# 04_Motor_Driver.net
KiCad netlist of a schematic drawn in Altium Designer
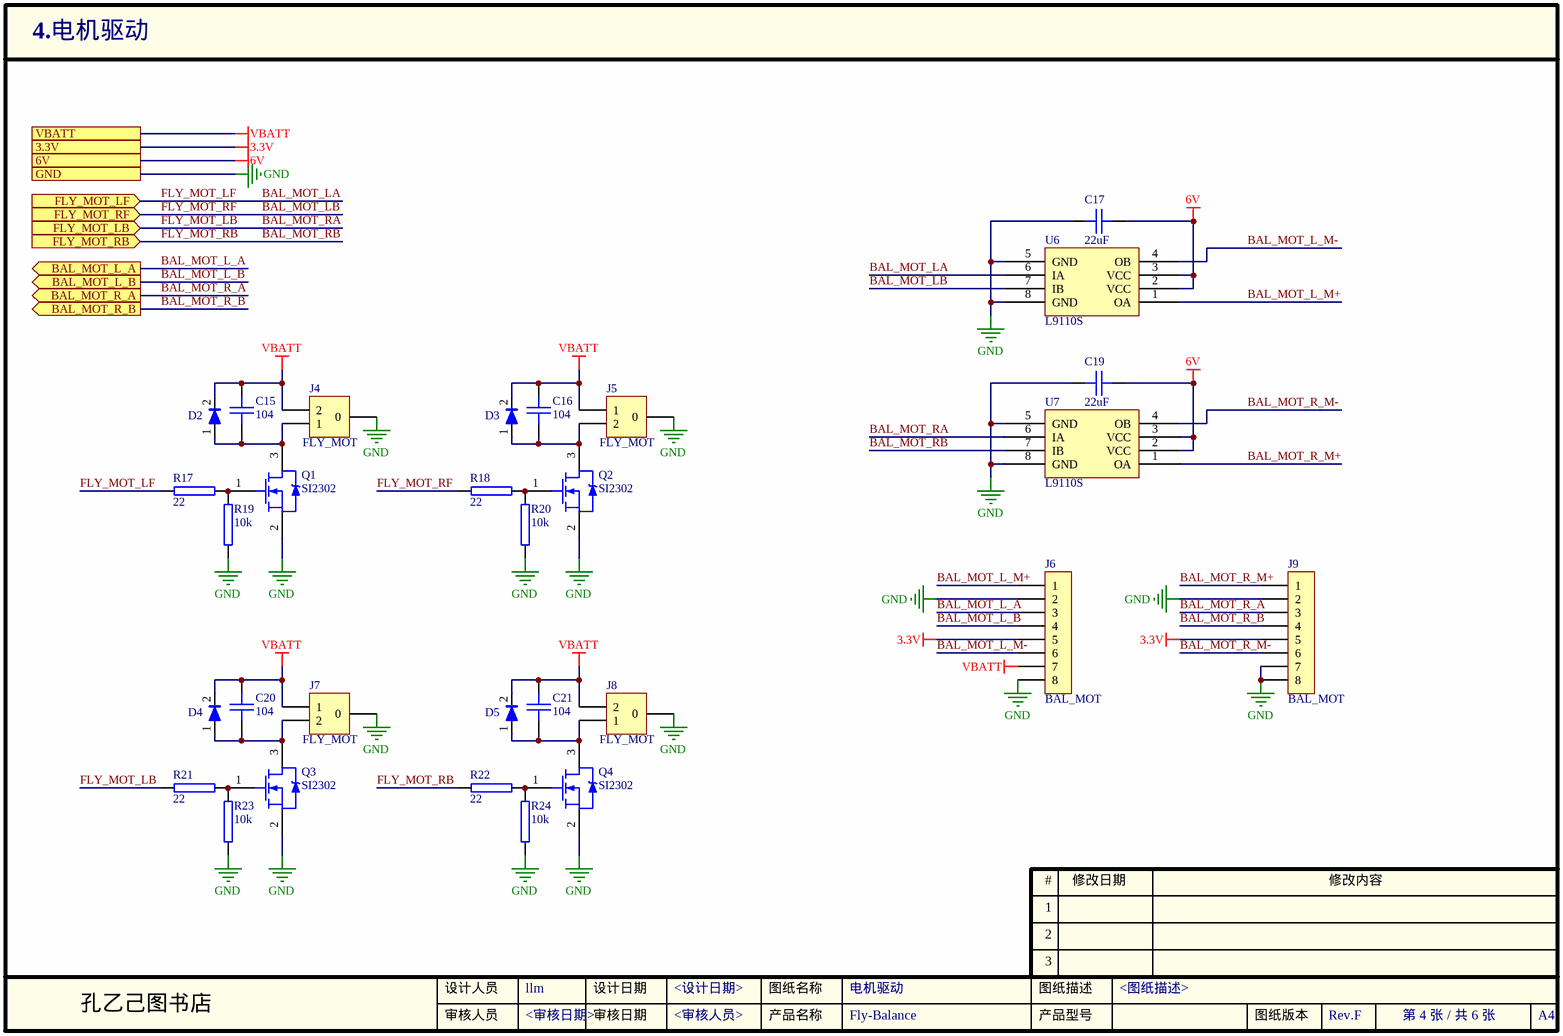
[diagram p0: 04_Motor_Driver.SchDoc]

(export (version "E")
  (design (tool "Eeschema 10.0.6"))
  (components
    (comp (ref "C15")
      (value "104")
      (footprint "0402C")
      (description "电容")
      (libsource (lib "MY_Schlib") (part "CAP"))
    )
    (comp (ref "C16")
      (value "104")
      (footprint "0402C")
      (description "电容")
      (libsource (lib "MY_Schlib") (part "CAP"))
    )
    (comp (ref "C17")
      (value "22uF")
      (footprint "0805C")
      (description "电容")
      (libsource (lib "MY_Schlib") (part "CAP"))
    )
    (comp (ref "C19")
      (value "22uF")
      (footprint "0805C")
      (description "电容")
      (libsource (lib "MY_Schlib") (part "CAP"))
    )
    (comp (ref "C20")
      (value "104")
      (footprint "0402C")
      (description "电容")
      (libsource (lib "MY_Schlib") (part "CAP"))
    )
    (comp (ref "C21")
      (value "104")
      (footprint "0402C")
      (description "电容")
      (libsource (lib "MY_Schlib") (part "CAP"))
    )
    (comp (ref "D2")
      (value "1N4001")
      (footprint "SOD-323")
      (description "二极管")
      (libsource (lib "MY_Schlib") (part "DIODE"))
    )
    (comp (ref "D3")
      (value "1N4001")
      (footprint "SOD-323")
      (description "二极管")
      (libsource (lib "MY_Schlib") (part "DIODE"))
    )
    (comp (ref "D4")
      (value "1N4001")
      (footprint "SOD-323")
      (description "二极管")
      (libsource (lib "MY_Schlib") (part "DIODE"))
    )
    (comp (ref "D5")
      (value "1N4001")
      (footprint "SOD-323")
      (description "二极管")
      (libsource (lib "MY_Schlib") (part "DIODE"))
    )
    (comp (ref "J4")
      (value "FLY_MOT")
      (footprint "CONN-SMD_2P-P1.25")
      (description "直流电机接口")
      (libsource (lib "") (part "CON_1"))
    )
    (comp (ref "J5")
      (value "FLY_MOT")
      (footprint "CONN-SMD_2P-P1.25")
      (description "直流电机接口")
      (libsource (lib "Schlib") (part "CON"))
    )
    (comp (ref "J6")
      (value "BAL_MOT")
      (footprint "CONN-SMD_6P-P2.00_DEALON_PH-6PWB")
      (description "Connector")
      (libsource (lib "MY_Schlib") (part "CON8"))
    )
    (comp (ref "J7")
      (value "FLY_MOT")
      (footprint "CONN-SMD_2P-P1.25")
      (description "直流电机接口")
      (libsource (lib "Schlib") (part "CON"))
    )
    (comp (ref "J8")
      (value "FLY_MOT")
      (footprint "CONN-SMD_2P-P1.25")
      (description "直流电机接口")
      (libsource (lib "") (part "CON_1"))
    )
    (comp (ref "J9")
      (value "BAL_MOT")
      (footprint "CONN-SMD_6P-P2.00_DEALON_PH-6PWB")
      (description "Connector")
      (libsource (lib "MY_Schlib") (part "CON8"))
    )
    (comp (ref "Q1")
      (value "SI2302")
      (footprint "SOT-23")
      (description "N-MOSFET")
      (libsource (lib "MY_Schlib") (part "N-MOS"))
    )
    (comp (ref "Q2")
      (value "SI2302")
      (footprint "SOT-23")
      (description "N-MOSFET")
      (libsource (lib "MY_Schlib") (part "N-MOS"))
    )
    (comp (ref "Q3")
      (value "SI2302")
      (footprint "SOT-23")
      (description "N-MOSFET")
      (libsource (lib "MY_Schlib") (part "N-MOS"))
    )
    (comp (ref "Q4")
      (value "SI2302")
      (footprint "SOT-23")
      (description "N-MOSFET")
      (libsource (lib "MY_Schlib") (part "N-MOS"))
    )
    (comp (ref "R17")
      (value "22")
      (footprint "0402R")
      (description "电阻")
      (libsource (lib "MY_Schlib") (part "RES"))
    )
    (comp (ref "R18")
      (value "22")
      (footprint "0402R")
      (description "电阻")
      (libsource (lib "MY_Schlib") (part "RES"))
    )
    (comp (ref "R19")
      (value "10k")
      (footprint "0402R")
      (description "电阻")
      (libsource (lib "MY_Schlib") (part "RES"))
    )
    (comp (ref "R20")
      (value "10k")
      (footprint "0402R")
      (description "电阻")
      (libsource (lib "MY_Schlib") (part "RES"))
    )
    (comp (ref "R21")
      (value "22")
      (footprint "0402R")
      (description "电阻")
      (libsource (lib "MY_Schlib") (part "RES"))
    )
    (comp (ref "R22")
      (value "22")
      (footprint "0402R")
      (description "电阻")
      (libsource (lib "MY_Schlib") (part "RES"))
    )
    (comp (ref "R23")
      (value "10k")
      (footprint "0402R")
      (description "电阻")
      (libsource (lib "MY_Schlib") (part "RES"))
    )
    (comp (ref "R24")
      (value "10k")
      (footprint "0402R")
      (description "电阻")
      (libsource (lib "MY_Schlib") (part "RES"))
    )
    (comp (ref "U6")
      (value "L9110S")
      (footprint "SOP-8_L4.9-W3.9-P1.27-LS6.0-BL")
      (description "H桥电机驱动芯片")
      (libsource (lib "MY_Schlib") (part "L9110S"))
    )
    (comp (ref "U7")
      (value "L9110S")
      (footprint "SOP-8_L4.9-W3.9-P1.27-LS6.0-BL")
      (description "H桥电机驱动芯片")
      (libsource (lib "MY_Schlib") (part "L9110S"))
    )
  )
  (nets
    (net (code "1") (name "/BAL_MOT_LA") (class "Default")
      (node (ref "R17") (pin "2") (pinfunction "2_2") (pintype "passive"))
      (node (ref "U6") (pin "6") (pinfunction "IA_6") (pintype "passive"))
    )
    (net (code "2") (name "/BAL_MOT_LB") (class "Default")
      (node (ref "R18") (pin "2") (pinfunction "2_2") (pintype "passive"))
      (node (ref "U6") (pin "7") (pinfunction "IB_7") (pintype "passive"))
    )
    (net (code "3") (name "/BAL_MOT_L_A") (class "Default")
      (node (ref "J6") (pin "3") (pinfunction "3_3") (pintype "passive"))
    )
    (net (code "4") (name "/BAL_MOT_L_B") (class "Default")
      (node (ref "J6") (pin "4") (pinfunction "4_4") (pintype "passive"))
    )
    (net (code "5") (name "/BAL_MOT_L_M+") (class "Default")
      (node (ref "J6") (pin "1") (pinfunction "1_1") (pintype "passive"))
      (node (ref "U6") (pin "1") (pinfunction "OA_1") (pintype "passive"))
    )
    (net (code "6") (name "/BAL_MOT_L_M-") (class "Default")
      (node (ref "J6") (pin "6") (pinfunction "6_6") (pintype "passive"))
      (node (ref "U6") (pin "4") (pinfunction "OB_4") (pintype "passive"))
    )
    (net (code "7") (name "/BAL_MOT_RA") (class "Default")
      (node (ref "R21") (pin "2") (pinfunction "2_2") (pintype "passive"))
      (node (ref "U7") (pin "6") (pinfunction "IA_6") (pintype "passive"))
    )
    (net (code "8") (name "/BAL_MOT_RB") (class "Default")
      (node (ref "R22") (pin "2") (pinfunction "2_2") (pintype "passive"))
      (node (ref "U7") (pin "7") (pinfunction "IB_7") (pintype "passive"))
    )
    (net (code "9") (name "/BAL_MOT_R_A") (class "Default")
      (node (ref "J9") (pin "3") (pinfunction "3_3") (pintype "passive"))
    )
    (net (code "10") (name "/BAL_MOT_R_B") (class "Default")
      (node (ref "J9") (pin "4") (pinfunction "4_4") (pintype "passive"))
    )
    (net (code "11") (name "/BAL_MOT_R_M+") (class "Default")
      (node (ref "J9") (pin "1") (pinfunction "1_1") (pintype "passive"))
      (node (ref "U7") (pin "1") (pinfunction "OA_1") (pintype "passive"))
    )
    (net (code "12") (name "/BAL_MOT_R_M-") (class "Default")
      (node (ref "J9") (pin "6") (pinfunction "6_6") (pintype "passive"))
      (node (ref "U7") (pin "4") (pinfunction "OB_4") (pintype "passive"))
    )
    (net (code "13") (name "3.3V") (class "Default")
      (node (ref "J6") (pin "5") (pinfunction "5_5") (pintype "passive"))
      (node (ref "J9") (pin "5") (pinfunction "5_5") (pintype "passive"))
    )
    (net (code "14") (name "6V") (class "Default")
      (node (ref "C17") (pin "1") (pinfunction "1_1") (pintype "passive"))
      (node (ref "C19") (pin "1") (pinfunction "1_1") (pintype "passive"))
      (node (ref "U6") (pin "2") (pinfunction "VCC_2") (pintype "passive"))
      (node (ref "U6") (pin "3") (pinfunction "VCC_3") (pintype "passive"))
      (node (ref "U7") (pin "2") (pinfunction "VCC_2") (pintype "passive"))
      (node (ref "U7") (pin "3") (pinfunction "VCC_3") (pintype "passive"))
    )
    (net (code "15") (name "GND") (class "Default")
      (node (ref "C17") (pin "2") (pinfunction "2_2") (pintype "passive"))
      (node (ref "C19") (pin "2") (pinfunction "2_2") (pintype "passive"))
      (node (ref "J4") (pin "0") (pinfunction "0_0") (pintype "passive"))
      (node (ref "J5") (pin "0") (pinfunction "0_0") (pintype "passive"))
      (node (ref "J6") (pin "2") (pinfunction "2_2") (pintype "passive"))
      (node (ref "J6") (pin "8") (pinfunction "8_8") (pintype "passive"))
      (node (ref "J7") (pin "0") (pinfunction "0_0") (pintype "passive"))
      (node (ref "J8") (pin "0") (pinfunction "0_0") (pintype "passive"))
      (node (ref "J9") (pin "2") (pinfunction "2_2") (pintype "passive"))
      (node (ref "J9") (pin "7") (pinfunction "7_7") (pintype "passive"))
      (node (ref "J9") (pin "8") (pinfunction "8_8") (pintype "passive"))
      (node (ref "Q1") (pin "2") (pinfunction "S_2") (pintype "passive"))
      (node (ref "Q2") (pin "2") (pinfunction "S_2") (pintype "passive"))
      (node (ref "Q3") (pin "2") (pinfunction "S_2") (pintype "passive"))
      (node (ref "Q4") (pin "2") (pinfunction "S_2") (pintype "passive"))
      (node (ref "R19") (pin "2") (pinfunction "2_2") (pintype "passive"))
      (node (ref "R20") (pin "2") (pinfunction "2_2") (pintype "passive"))
      (node (ref "R23") (pin "2") (pinfunction "2_2") (pintype "passive"))
      (node (ref "R24") (pin "2") (pinfunction "2_2") (pintype "passive"))
      (node (ref "U6") (pin "5") (pinfunction "GND_5") (pintype "passive"))
      (node (ref "U6") (pin "8") (pinfunction "GND_8") (pintype "passive"))
      (node (ref "U7") (pin "5") (pinfunction "GND_5") (pintype "passive"))
      (node (ref "U7") (pin "8") (pinfunction "GND_8") (pintype "passive"))
    )
    (net (code "16") (name "Net-(Q1-D)") (class "Default")
      (node (ref "C15") (pin "2") (pinfunction "2_2") (pintype "passive"))
      (node (ref "D2") (pin "1") (pinfunction "1_1") (pintype "passive"))
      (node (ref "J4") (pin "1") (pinfunction "1_1") (pintype "passive"))
      (node (ref "Q1") (pin "3") (pinfunction "D_3") (pintype "passive"))
    )
    (net (code "17") (name "Net-(Q1-G)") (class "Default")
      (node (ref "Q1") (pin "1") (pinfunction "G_1") (pintype "passive"))
      (node (ref "R17") (pin "1") (pinfunction "1_1") (pintype "passive"))
      (node (ref "R19") (pin "1") (pinfunction "1_1") (pintype "passive"))
    )
    (net (code "18") (name "Net-(Q2-D)") (class "Default")
      (node (ref "C16") (pin "2") (pinfunction "2_2") (pintype "passive"))
      (node (ref "D3") (pin "1") (pinfunction "1_1") (pintype "passive"))
      (node (ref "J5") (pin "2") (pinfunction "2_2") (pintype "passive"))
      (node (ref "Q2") (pin "3") (pinfunction "D_3") (pintype "passive"))
    )
    (net (code "19") (name "Net-(Q2-G)") (class "Default")
      (node (ref "Q2") (pin "1") (pinfunction "G_1") (pintype "passive"))
      (node (ref "R18") (pin "1") (pinfunction "1_1") (pintype "passive"))
      (node (ref "R20") (pin "1") (pinfunction "1_1") (pintype "passive"))
    )
    (net (code "20") (name "Net-(Q3-D)") (class "Default")
      (node (ref "C20") (pin "2") (pinfunction "2_2") (pintype "passive"))
      (node (ref "D4") (pin "1") (pinfunction "1_1") (pintype "passive"))
      (node (ref "J7") (pin "2") (pinfunction "2_2") (pintype "passive"))
      (node (ref "Q3") (pin "3") (pinfunction "D_3") (pintype "passive"))
    )
    (net (code "21") (name "Net-(Q3-G)") (class "Default")
      (node (ref "Q3") (pin "1") (pinfunction "G_1") (pintype "passive"))
      (node (ref "R21") (pin "1") (pinfunction "1_1") (pintype "passive"))
      (node (ref "R23") (pin "1") (pinfunction "1_1") (pintype "passive"))
    )
    (net (code "22") (name "Net-(Q4-D)") (class "Default")
      (node (ref "C21") (pin "2") (pinfunction "2_2") (pintype "passive"))
      (node (ref "D5") (pin "1") (pinfunction "1_1") (pintype "passive"))
      (node (ref "J8") (pin "1") (pinfunction "1_1") (pintype "passive"))
      (node (ref "Q4") (pin "3") (pinfunction "D_3") (pintype "passive"))
    )
    (net (code "23") (name "Net-(Q4-G)") (class "Default")
      (node (ref "Q4") (pin "1") (pinfunction "G_1") (pintype "passive"))
      (node (ref "R22") (pin "1") (pinfunction "1_1") (pintype "passive"))
      (node (ref "R24") (pin "1") (pinfunction "1_1") (pintype "passive"))
    )
    (net (code "24") (name "VBATT") (class "Default")
      (node (ref "C15") (pin "1") (pinfunction "1_1") (pintype "passive"))
      (node (ref "C16") (pin "1") (pinfunction "1_1") (pintype "passive"))
      (node (ref "C20") (pin "1") (pinfunction "1_1") (pintype "passive"))
      (node (ref "C21") (pin "1") (pinfunction "1_1") (pintype "passive"))
      (node (ref "D2") (pin "2") (pinfunction "2_2") (pintype "passive"))
      (node (ref "D3") (pin "2") (pinfunction "2_2") (pintype "passive"))
      (node (ref "D4") (pin "2") (pinfunction "2_2") (pintype "passive"))
      (node (ref "D5") (pin "2") (pinfunction "2_2") (pintype "passive"))
      (node (ref "J4") (pin "2") (pinfunction "2_2") (pintype "passive"))
      (node (ref "J5") (pin "1") (pinfunction "1_1") (pintype "passive"))
      (node (ref "J6") (pin "7") (pinfunction "7_7") (pintype "passive"))
      (node (ref "J7") (pin "1") (pinfunction "1_1") (pintype "passive"))
      (node (ref "J8") (pin "2") (pinfunction "2_2") (pintype "passive"))
    )
  )
)
